# rescue_linea5cny.net
KiCad netlist of a schematic drawn in EAGLE
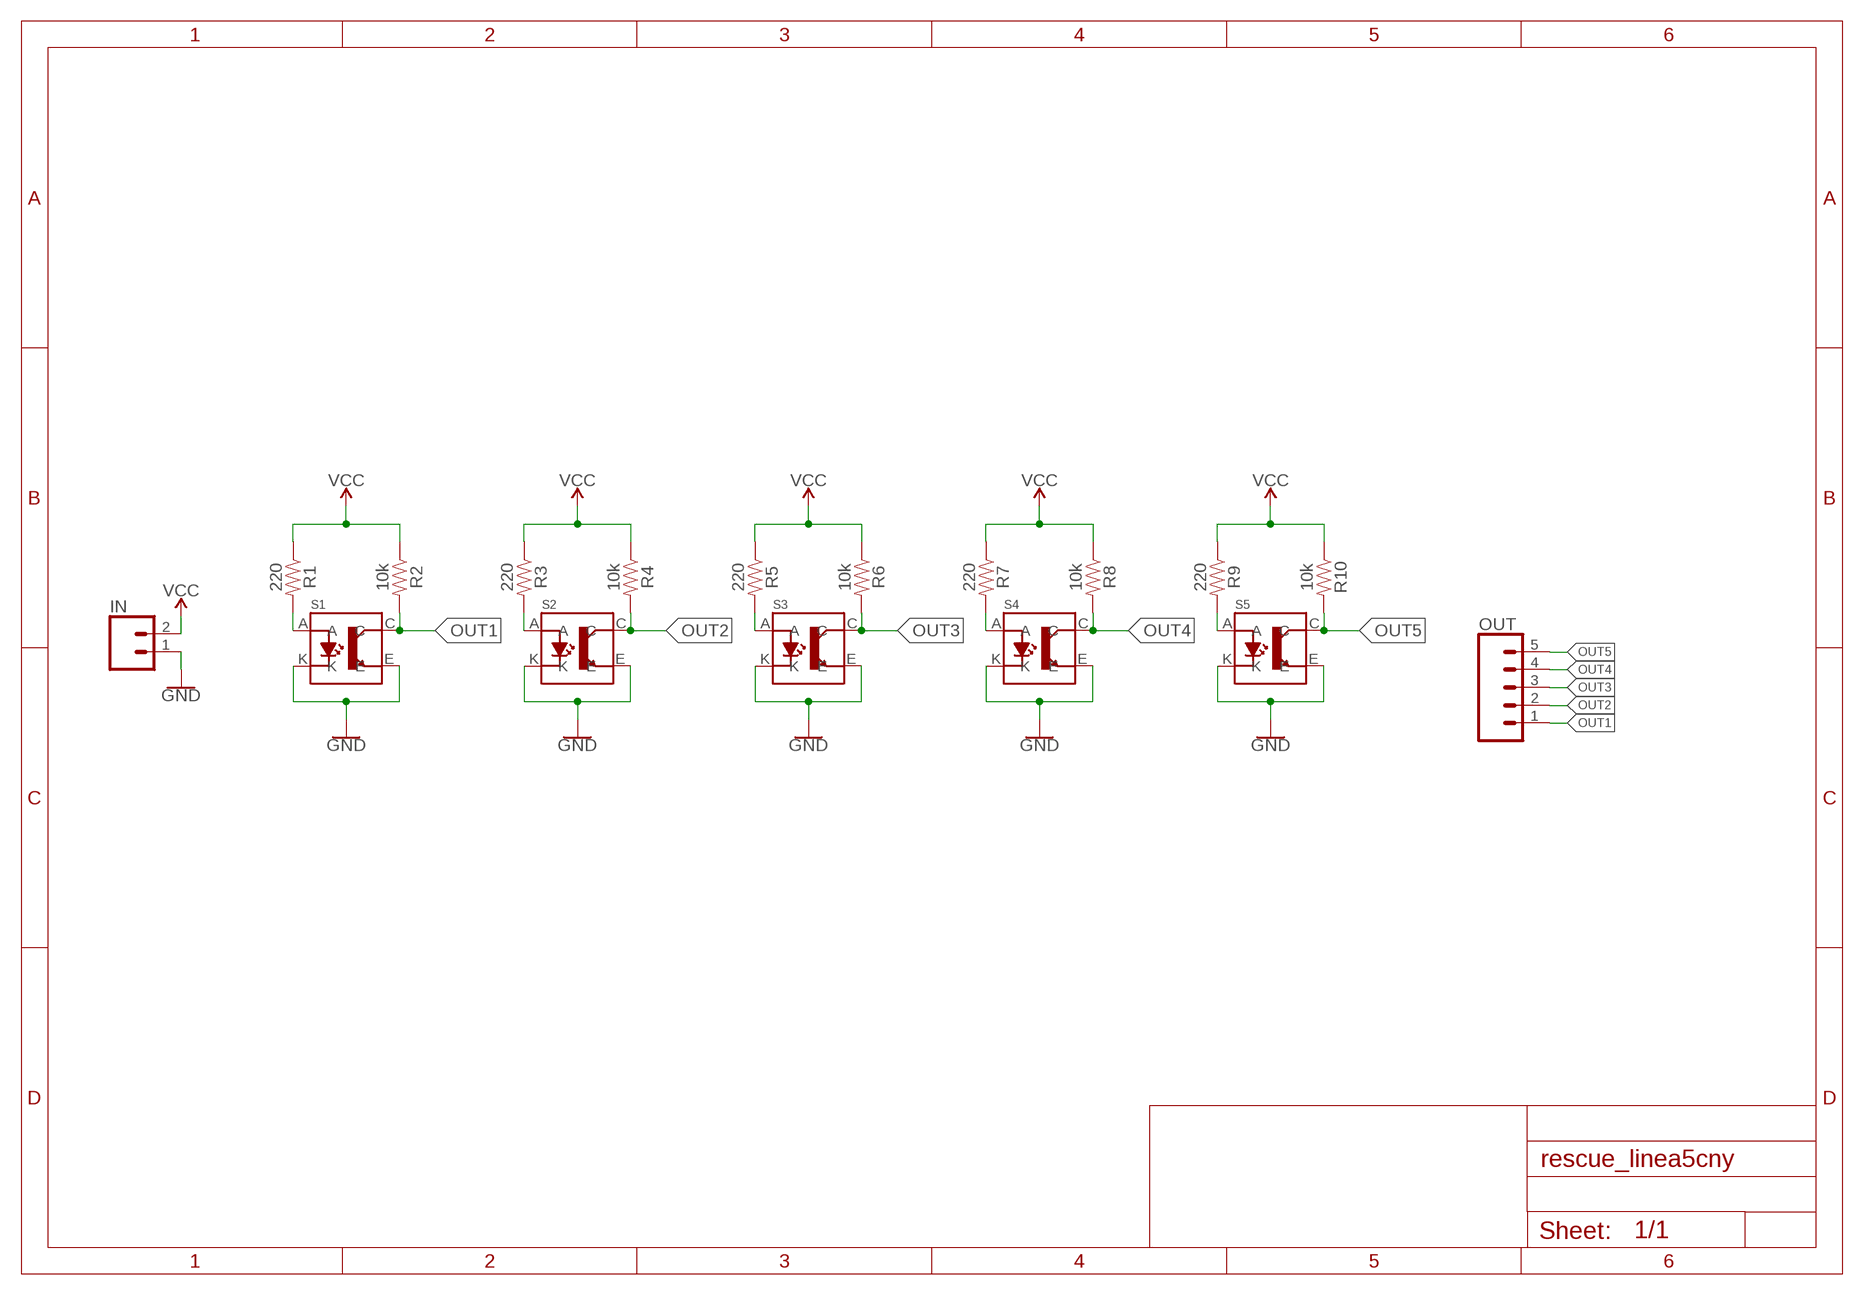
[diagram p0: schematic, sheet 1]

(export (version "E")
  (design (tool "Eeschema 10.0.6"))
  (components
    (comp (ref "IN")
      (value "CONN_02")
      (footprint "eagle-import:1X02")
      (libsource (lib "eagle-import") (part "CONN_02"))
    )
    (comp (ref "OUT")
      (value "CONN_05")
      (footprint "eagle-import:1X05")
      (libsource (lib "eagle-import") (part "CONN_05"))
    )
    (comp (ref "R1")
      (value "220")
      (footprint "eagle-import:AXIAL-0.3")
      (libsource (lib "eagle-import") (part "RESISTORAXIAL-0.3"))
    )
    (comp (ref "R2")
      (value "10k")
      (footprint "eagle-import:AXIAL-0.3")
      (libsource (lib "eagle-import") (part "RESISTORAXIAL-0.3"))
    )
    (comp (ref "R3")
      (value "220")
      (footprint "eagle-import:AXIAL-0.3")
      (libsource (lib "eagle-import") (part "RESISTORAXIAL-0.3"))
    )
    (comp (ref "R4")
      (value "10k")
      (footprint "eagle-import:AXIAL-0.3")
      (libsource (lib "eagle-import") (part "RESISTORAXIAL-0.3"))
    )
    (comp (ref "R5")
      (value "220")
      (footprint "eagle-import:AXIAL-0.3")
      (libsource (lib "eagle-import") (part "RESISTORAXIAL-0.3"))
    )
    (comp (ref "R6")
      (value "10k")
      (footprint "eagle-import:AXIAL-0.3")
      (libsource (lib "eagle-import") (part "RESISTORAXIAL-0.3"))
    )
    (comp (ref "R7")
      (value "220")
      (footprint "eagle-import:AXIAL-0.3")
      (libsource (lib "eagle-import") (part "RESISTORAXIAL-0.3"))
    )
    (comp (ref "R8")
      (value "10k")
      (footprint "eagle-import:AXIAL-0.3")
      (libsource (lib "eagle-import") (part "RESISTORAXIAL-0.3"))
    )
    (comp (ref "R9")
      (value "220")
      (footprint "eagle-import:AXIAL-0.3")
      (libsource (lib "eagle-import") (part "RESISTORAXIAL-0.3"))
    )
    (comp (ref "R10")
      (value "10k")
      (footprint "eagle-import:AXIAL-0.3")
      (libsource (lib "eagle-import") (part "RESISTORAXIAL-0.3"))
    )
    (comp (ref "S1")
      (value "CNY70")
      (footprint "eagle-import:CNY70")
      (libsource (lib "eagle-import") (part "CNY70"))
    )
    (comp (ref "S2")
      (value "CNY70")
      (footprint "eagle-import:CNY70")
      (libsource (lib "eagle-import") (part "CNY70"))
    )
    (comp (ref "S3")
      (value "CNY70")
      (footprint "eagle-import:CNY70")
      (libsource (lib "eagle-import") (part "CNY70"))
    )
    (comp (ref "S4")
      (value "CNY70")
      (footprint "eagle-import:CNY70")
      (libsource (lib "eagle-import") (part "CNY70"))
    )
    (comp (ref "S5")
      (value "CNY70")
      (footprint "eagle-import:CNY70")
      (libsource (lib "eagle-import") (part "CNY70"))
    )
  )
  (nets
    (net (code "1") (name "GND") (class "Default")
      (node (ref "IN") (pin "1") (pinfunction "1_1") (pintype "passive"))
      (node (ref "S1") (pin "E") (pinfunction "E_E") (pintype "bidirectional"))
      (node (ref "S1") (pin "K") (pinfunction "K_K") (pintype "bidirectional"))
      (node (ref "S2") (pin "E") (pinfunction "E_E") (pintype "bidirectional"))
      (node (ref "S2") (pin "K") (pinfunction "K_K") (pintype "bidirectional"))
      (node (ref "S3") (pin "E") (pinfunction "E_E") (pintype "bidirectional"))
      (node (ref "S3") (pin "K") (pinfunction "K_K") (pintype "bidirectional"))
      (node (ref "S4") (pin "E") (pinfunction "E_E") (pintype "bidirectional"))
      (node (ref "S4") (pin "K") (pinfunction "K_K") (pintype "bidirectional"))
      (node (ref "S5") (pin "E") (pinfunction "E_E") (pintype "bidirectional"))
      (node (ref "S5") (pin "K") (pinfunction "K_K") (pintype "bidirectional"))
    )
    (net (code "2") (name "Net-(R1-2)") (class "Default")
      (node (ref "R1") (pin "P$2") (pinfunction "2_P$2") (pintype "passive"))
      (node (ref "S1") (pin "A") (pinfunction "A_A") (pintype "bidirectional"))
    )
    (net (code "3") (name "Net-(R3-2)") (class "Default")
      (node (ref "R3") (pin "P$2") (pinfunction "2_P$2") (pintype "passive"))
      (node (ref "S2") (pin "A") (pinfunction "A_A") (pintype "bidirectional"))
    )
    (net (code "4") (name "Net-(R5-2)") (class "Default")
      (node (ref "R5") (pin "P$2") (pinfunction "2_P$2") (pintype "passive"))
      (node (ref "S3") (pin "A") (pinfunction "A_A") (pintype "bidirectional"))
    )
    (net (code "5") (name "Net-(R7-2)") (class "Default")
      (node (ref "R7") (pin "P$2") (pinfunction "2_P$2") (pintype "passive"))
      (node (ref "S4") (pin "A") (pinfunction "A_A") (pintype "bidirectional"))
    )
    (net (code "6") (name "Net-(R9-2)") (class "Default")
      (node (ref "R9") (pin "P$2") (pinfunction "2_P$2") (pintype "passive"))
      (node (ref "S5") (pin "A") (pinfunction "A_A") (pintype "bidirectional"))
    )
    (net (code "7") (name "OUT1") (class "Default")
      (node (ref "OUT") (pin "1") (pinfunction "1_1") (pintype "passive"))
      (node (ref "R2") (pin "P$2") (pinfunction "2_P$2") (pintype "passive"))
      (node (ref "S1") (pin "C") (pinfunction "C_C") (pintype "bidirectional"))
    )
    (net (code "8") (name "OUT2") (class "Default")
      (node (ref "OUT") (pin "2") (pinfunction "2_2") (pintype "passive"))
      (node (ref "R4") (pin "P$2") (pinfunction "2_P$2") (pintype "passive"))
      (node (ref "S2") (pin "C") (pinfunction "C_C") (pintype "bidirectional"))
    )
    (net (code "9") (name "OUT3") (class "Default")
      (node (ref "OUT") (pin "3") (pinfunction "3_3") (pintype "passive"))
      (node (ref "R6") (pin "P$2") (pinfunction "2_P$2") (pintype "passive"))
      (node (ref "S3") (pin "C") (pinfunction "C_C") (pintype "bidirectional"))
    )
    (net (code "10") (name "OUT4") (class "Default")
      (node (ref "OUT") (pin "4") (pinfunction "4_4") (pintype "passive"))
      (node (ref "R8") (pin "P$2") (pinfunction "2_P$2") (pintype "passive"))
      (node (ref "S4") (pin "C") (pinfunction "C_C") (pintype "bidirectional"))
    )
    (net (code "11") (name "OUT5") (class "Default")
      (node (ref "OUT") (pin "5") (pinfunction "5_5") (pintype "passive"))
      (node (ref "R10") (pin "P$2") (pinfunction "2_P$2") (pintype "passive"))
      (node (ref "S5") (pin "C") (pinfunction "C_C") (pintype "bidirectional"))
    )
    (net (code "12") (name "VCC") (class "Default")
      (node (ref "IN") (pin "2") (pinfunction "2_2") (pintype "passive"))
      (node (ref "R1") (pin "P$1") (pinfunction "1_P$1") (pintype "passive"))
      (node (ref "R10") (pin "P$1") (pinfunction "1_P$1") (pintype "passive"))
      (node (ref "R2") (pin "P$1") (pinfunction "1_P$1") (pintype "passive"))
      (node (ref "R3") (pin "P$1") (pinfunction "1_P$1") (pintype "passive"))
      (node (ref "R4") (pin "P$1") (pinfunction "1_P$1") (pintype "passive"))
      (node (ref "R5") (pin "P$1") (pinfunction "1_P$1") (pintype "passive"))
      (node (ref "R6") (pin "P$1") (pinfunction "1_P$1") (pintype "passive"))
      (node (ref "R7") (pin "P$1") (pinfunction "1_P$1") (pintype "passive"))
      (node (ref "R8") (pin "P$1") (pinfunction "1_P$1") (pintype "passive"))
      (node (ref "R9") (pin "P$1") (pinfunction "1_P$1") (pintype "passive"))
    )
  )
)
